# comcon_version_av_reducido.net
KiCad netlist of a schematic drawn in EAGLE
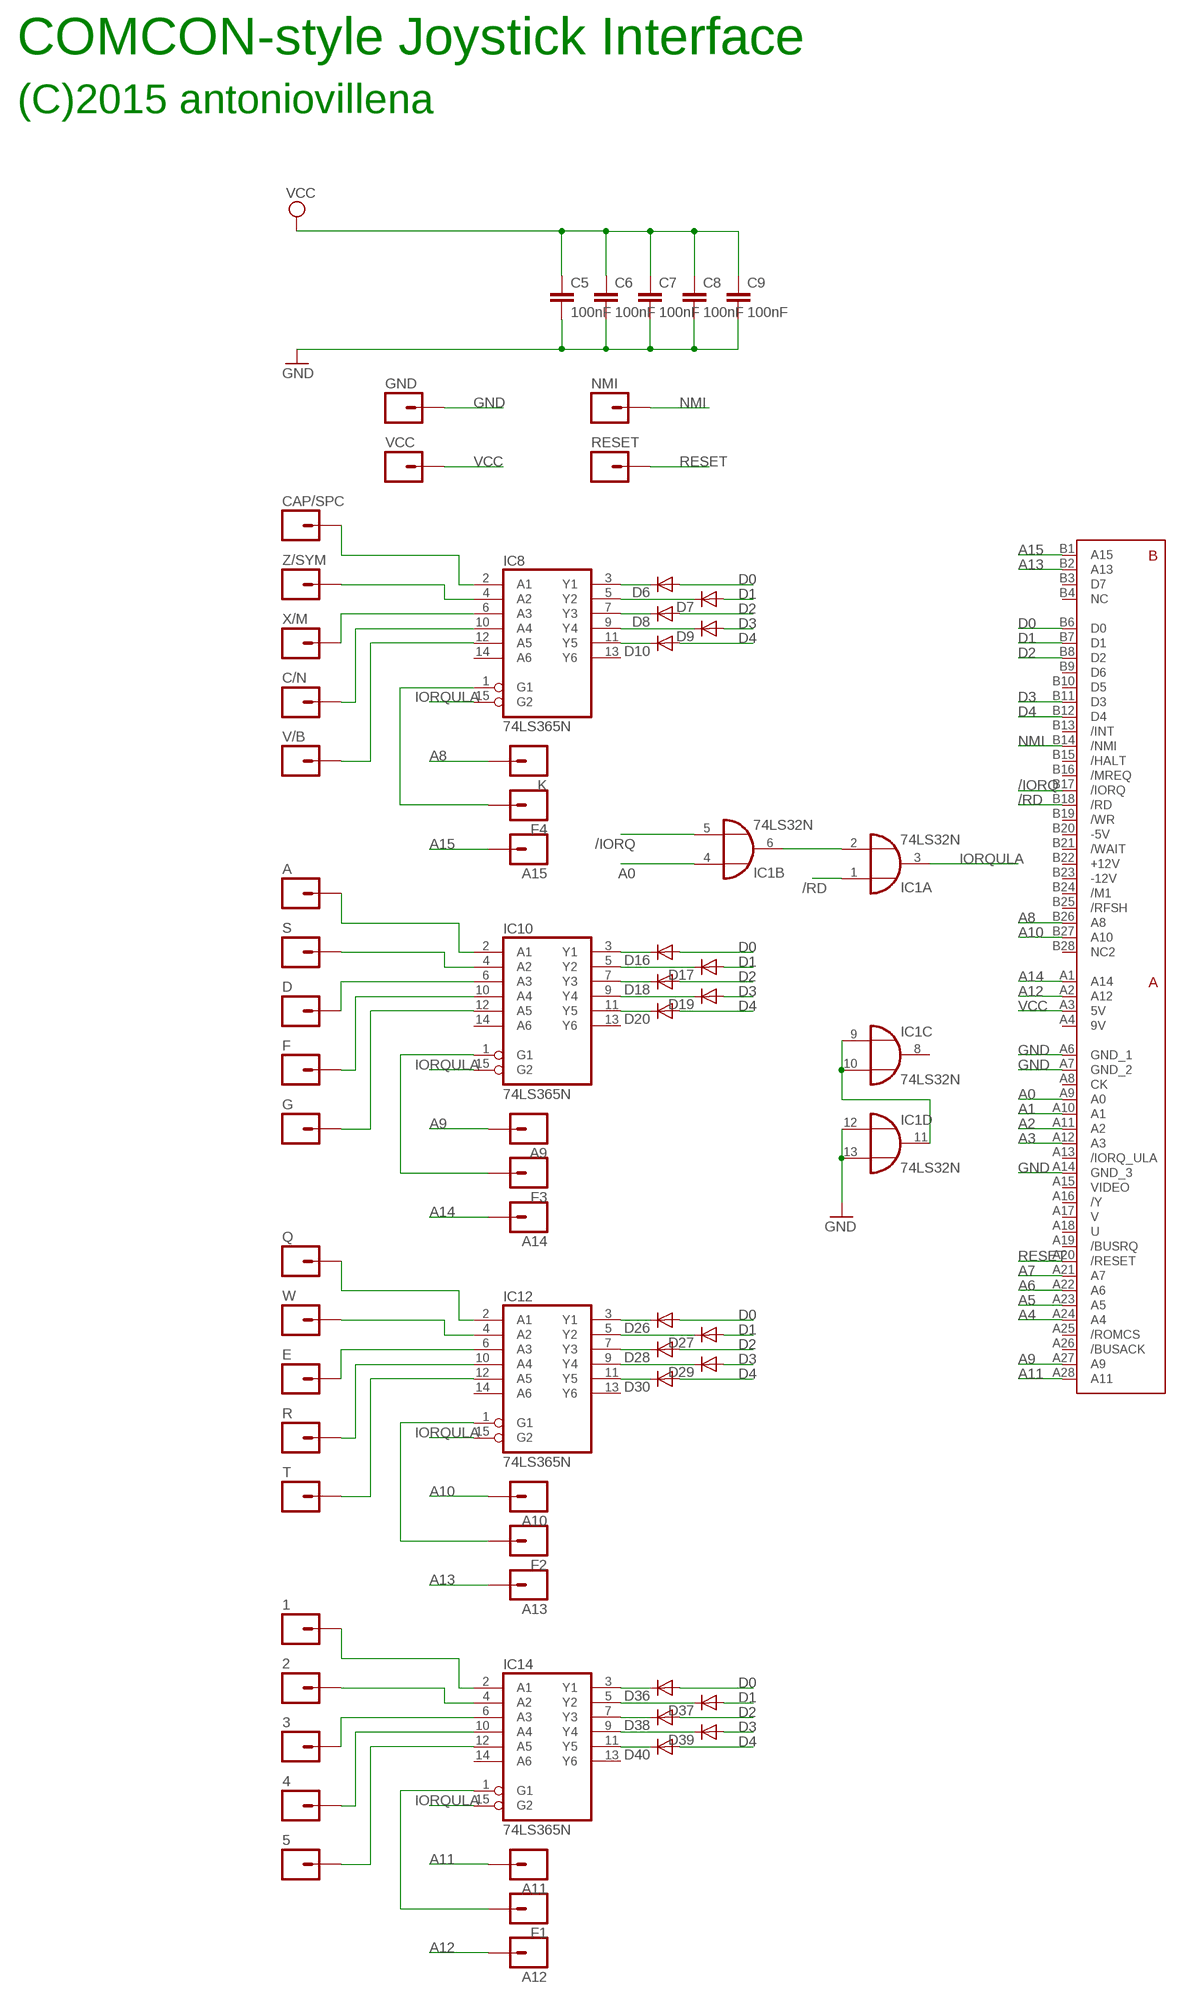
[diagram p0: schematic, sheet 1]

(export (version "E")
  (design (tool "Eeschema 10.0.6"))
  (components
    (comp (ref "1")
      (value "M01PTH")
      (footprint "eagle-import:1X01")
      (libsource (lib "eagle-import") (part "M01PTH"))
    )
    (comp (ref "2")
      (value "M01PTH")
      (footprint "eagle-import:1X01")
      (libsource (lib "eagle-import") (part "M01PTH"))
    )
    (comp (ref "3")
      (value "M01PTH")
      (footprint "eagle-import:1X01")
      (libsource (lib "eagle-import") (part "M01PTH"))
    )
    (comp (ref "4")
      (value "M01PTH")
      (footprint "eagle-import:1X01")
      (libsource (lib "eagle-import") (part "M01PTH"))
    )
    (comp (ref "5")
      (value "M01PTH")
      (footprint "eagle-import:1X01")
      (libsource (lib "eagle-import") (part "M01PTH"))
    )
    (comp (ref "A")
      (value "M01PTH")
      (footprint "eagle-import:1X01")
      (libsource (lib "eagle-import") (part "M01PTH"))
    )
    (comp (ref "A9")
      (value "M01PTH")
      (footprint "eagle-import:1X01")
      (libsource (lib "eagle-import") (part "M01PTH"))
    )
    (comp (ref "A10")
      (value "M01PTH")
      (footprint "eagle-import:1X01")
      (libsource (lib "eagle-import") (part "M01PTH"))
    )
    (comp (ref "A11")
      (value "M01PTH")
      (footprint "eagle-import:1X01")
      (libsource (lib "eagle-import") (part "M01PTH"))
    )
    (comp (ref "A12")
      (value "M01PTH")
      (footprint "eagle-import:1X01")
      (libsource (lib "eagle-import") (part "M01PTH"))
    )
    (comp (ref "A13")
      (value "M01PTH")
      (footprint "eagle-import:1X01")
      (libsource (lib "eagle-import") (part "M01PTH"))
    )
    (comp (ref "A14")
      (value "M01PTH")
      (footprint "eagle-import:1X01")
      (libsource (lib "eagle-import") (part "M01PTH"))
    )
    (comp (ref "A15")
      (value "M01PTH")
      (footprint "eagle-import:1X01")
      (libsource (lib "eagle-import") (part "M01PTH"))
    )
    (comp (ref "C/N")
      (value "M01PTH")
      (footprint "eagle-import:1X01")
      (libsource (lib "eagle-import") (part "M01PTH"))
    )
    (comp (ref "C5")
      (value "100nF")
      (footprint "eagle-import:C050-025X075")
      (libsource (lib "eagle-import") (part "C-EU050-025X075"))
    )
    (comp (ref "C6")
      (value "100nF")
      (footprint "eagle-import:C050-025X075")
      (libsource (lib "eagle-import") (part "C-EU050-025X075"))
    )
    (comp (ref "C7")
      (value "100nF")
      (footprint "eagle-import:C050-025X075")
      (libsource (lib "eagle-import") (part "C-EU050-025X075"))
    )
    (comp (ref "C8")
      (value "100nF")
      (footprint "eagle-import:C050-025X075")
      (libsource (lib "eagle-import") (part "C-EU050-025X075"))
    )
    (comp (ref "C9")
      (value "100nF")
      (footprint "eagle-import:C050-025X075")
      (libsource (lib "eagle-import") (part "C-EU050-025X075"))
    )
    (comp (ref "CAP/SPC")
      (value "M01PTH")
      (footprint "eagle-import:1X01")
      (libsource (lib "eagle-import") (part "M01PTH"))
    )
    (comp (ref "D")
      (value "M01PTH")
      (footprint "eagle-import:1X01")
      (libsource (lib "eagle-import") (part "M01PTH"))
    )
    (comp (ref "D6")
      (value "1N4148DO35-7")
      (footprint "eagle-import:DO35-7")
      (libsource (lib "eagle-import") (part "1N4148DO35-7"))
    )
    (comp (ref "D7")
      (value "1N4148DO35-7")
      (footprint "eagle-import:DO35-7")
      (libsource (lib "eagle-import") (part "1N4148DO35-7"))
    )
    (comp (ref "D8")
      (value "1N4148DO35-7")
      (footprint "eagle-import:DO35-7")
      (libsource (lib "eagle-import") (part "1N4148DO35-7"))
    )
    (comp (ref "D9")
      (value "1N4148DO35-7")
      (footprint "eagle-import:DO35-7")
      (libsource (lib "eagle-import") (part "1N4148DO35-7"))
    )
    (comp (ref "D10")
      (value "1N4148DO35-7")
      (footprint "eagle-import:DO35-7")
      (libsource (lib "eagle-import") (part "1N4148DO35-7"))
    )
    (comp (ref "D16")
      (value "1N4148DO35-7")
      (footprint "eagle-import:DO35-7")
      (libsource (lib "eagle-import") (part "1N4148DO35-7"))
    )
    (comp (ref "D17")
      (value "1N4148DO35-7")
      (footprint "eagle-import:DO35-7")
      (libsource (lib "eagle-import") (part "1N4148DO35-7"))
    )
    (comp (ref "D18")
      (value "1N4148DO35-7")
      (footprint "eagle-import:DO35-7")
      (libsource (lib "eagle-import") (part "1N4148DO35-7"))
    )
    (comp (ref "D19")
      (value "1N4148DO35-7")
      (footprint "eagle-import:DO35-7")
      (libsource (lib "eagle-import") (part "1N4148DO35-7"))
    )
    (comp (ref "D20")
      (value "1N4148DO35-7")
      (footprint "eagle-import:DO35-7")
      (libsource (lib "eagle-import") (part "1N4148DO35-7"))
    )
    (comp (ref "D26")
      (value "1N4148DO35-7")
      (footprint "eagle-import:DO35-7")
      (libsource (lib "eagle-import") (part "1N4148DO35-7"))
    )
    (comp (ref "D27")
      (value "1N4148DO35-7")
      (footprint "eagle-import:DO35-7")
      (libsource (lib "eagle-import") (part "1N4148DO35-7"))
    )
    (comp (ref "D28")
      (value "1N4148DO35-7")
      (footprint "eagle-import:DO35-7")
      (libsource (lib "eagle-import") (part "1N4148DO35-7"))
    )
    (comp (ref "D29")
      (value "1N4148DO35-7")
      (footprint "eagle-import:DO35-7")
      (libsource (lib "eagle-import") (part "1N4148DO35-7"))
    )
    (comp (ref "D30")
      (value "1N4148DO35-7")
      (footprint "eagle-import:DO35-7")
      (libsource (lib "eagle-import") (part "1N4148DO35-7"))
    )
    (comp (ref "D36")
      (value "1N4148DO35-7")
      (footprint "eagle-import:DO35-7")
      (libsource (lib "eagle-import") (part "1N4148DO35-7"))
    )
    (comp (ref "D37")
      (value "1N4148DO35-7")
      (footprint "eagle-import:DO35-7")
      (libsource (lib "eagle-import") (part "1N4148DO35-7"))
    )
    (comp (ref "D38")
      (value "1N4148DO35-7")
      (footprint "eagle-import:DO35-7")
      (libsource (lib "eagle-import") (part "1N4148DO35-7"))
    )
    (comp (ref "D39")
      (value "1N4148DO35-7")
      (footprint "eagle-import:DO35-7")
      (libsource (lib "eagle-import") (part "1N4148DO35-7"))
    )
    (comp (ref "D40")
      (value "1N4148DO35-7")
      (footprint "eagle-import:DO35-7")
      (libsource (lib "eagle-import") (part "1N4148DO35-7"))
    )
    (comp (ref "E")
      (value "M01PTH")
      (footprint "eagle-import:1X01")
      (libsource (lib "eagle-import") (part "M01PTH"))
    )
    (comp (ref "F")
      (value "M01PTH")
      (footprint "eagle-import:1X01")
      (libsource (lib "eagle-import") (part "M01PTH"))
    )
    (comp (ref "F1")
      (value "M01PTH")
      (footprint "eagle-import:1X01")
      (libsource (lib "eagle-import") (part "M01PTH"))
    )
    (comp (ref "F2")
      (value "M01PTH")
      (footprint "eagle-import:1X01")
      (libsource (lib "eagle-import") (part "M01PTH"))
    )
    (comp (ref "F3")
      (value "M01PTH")
      (footprint "eagle-import:1X01")
      (libsource (lib "eagle-import") (part "M01PTH"))
    )
    (comp (ref "F4")
      (value "M01PTH")
      (footprint "eagle-import:1X01")
      (libsource (lib "eagle-import") (part "M01PTH"))
    )
    (comp (ref "G")
      (value "M01PTH")
      (footprint "eagle-import:1X01")
      (libsource (lib "eagle-import") (part "M01PTH"))
    )
    (comp (ref "GND")
      (value "M01PTH")
      (footprint "eagle-import:1X01")
      (libsource (lib "eagle-import") (part "M01PTH"))
    )
    (comp (ref "IC1")
      (value "74LS32N")
      (footprint "eagle-import:DIL14")
      (libsource (lib "eagle-import") (part "7432NLS"))
    )
    (comp (ref "IC8")
      (value "74LS365N")
      (footprint "eagle-import:DIL16")
      (libsource (lib "eagle-import") (part "74365NHC"))
    )
    (comp (ref "IC10")
      (value "74LS365N")
      (footprint "eagle-import:DIL16")
      (libsource (lib "eagle-import") (part "74365NHC"))
    )
    (comp (ref "IC12")
      (value "74LS365N")
      (footprint "eagle-import:DIL16")
      (libsource (lib "eagle-import") (part "74365NHC"))
    )
    (comp (ref "IC14")
      (value "74LS365N")
      (footprint "eagle-import:DIL16")
      (libsource (lib "eagle-import") (part "74365NHC"))
    )
    (comp (ref "K")
      (value "M01PTH")
      (footprint "eagle-import:1X01")
      (libsource (lib "eagle-import") (part "M01PTH"))
    )
    (comp (ref "NMI")
      (value "M01PTH")
      (footprint "eagle-import:1X01")
      (libsource (lib "eagle-import") (part "M01PTH"))
    )
    (comp (ref "Q")
      (value "M01PTH")
      (footprint "eagle-import:1X01")
      (libsource (lib "eagle-import") (part "M01PTH"))
    )
    (comp (ref "R")
      (value "M01PTH")
      (footprint "eagle-import:1X01")
      (libsource (lib "eagle-import") (part "M01PTH"))
    )
    (comp (ref "RESET")
      (value "M01PTH")
      (footprint "eagle-import:1X01")
      (libsource (lib "eagle-import") (part "M01PTH"))
    )
    (comp (ref "S")
      (value "M01PTH")
      (footprint "eagle-import:1X01")
      (libsource (lib "eagle-import") (part "M01PTH"))
    )
    (comp (ref "T")
      (value "M01PTH")
      (footprint "eagle-import:1X01")
      (libsource (lib "eagle-import") (part "M01PTH"))
    )
    (comp (ref "U$3")
      (value "ZXSP_ED2X28_SPE")
      (footprint "eagle-import:2X28_SPE")
      (libsource (lib "eagle-import") (part "ZXSP_ED2X28_SPE"))
    )
    (comp (ref "V/B")
      (value "M01PTH")
      (footprint "eagle-import:1X01")
      (libsource (lib "eagle-import") (part "M01PTH"))
    )
    (comp (ref "VCC")
      (value "M01PTH")
      (footprint "eagle-import:1X01")
      (libsource (lib "eagle-import") (part "M01PTH"))
    )
    (comp (ref "W")
      (value "M01PTH")
      (footprint "eagle-import:1X01")
      (libsource (lib "eagle-import") (part "M01PTH"))
    )
    (comp (ref "X/M")
      (value "M01PTH")
      (footprint "eagle-import:1X01")
      (libsource (lib "eagle-import") (part "M01PTH"))
    )
    (comp (ref "Z/SYM")
      (value "M01PTH")
      (footprint "eagle-import:1X01")
      (libsource (lib "eagle-import") (part "M01PTH"))
    )
  )
  (nets
    (net (code "1") (name "/+12V") (class "Default")
      (node (ref "U$3") (pin "B22") (pinfunction "+12V_B22") (pintype "power_in"))
    )
    (net (code "2") (name "/-5V") (class "Default")
      (node (ref "U$3") (pin "B20") (pinfunction "-5V_B20") (pintype "power_in"))
    )
    (net (code "3") (name "/-12V") (class "Default")
      (node (ref "U$3") (pin "B23") (pinfunction "-12V_B23") (pintype "power_in"))
    )
    (net (code "4") (name "/9V") (class "Default")
      (node (ref "U$3") (pin "A4") (pinfunction "9V_A4") (pintype "power_in"))
    )
    (net (code "5") (name "/A0") (class "Default")
      (node (ref "IC1") (pin "4") (pinfunction "I0_4") (pintype "input"))
      (node (ref "U$3") (pin "A9") (pinfunction "A0_A9") (pintype "bidirectional"))
    )
    (net (code "6") (name "/A1") (class "Default")
      (node (ref "U$3") (pin "A10") (pinfunction "A1_A10") (pintype "bidirectional"))
    )
    (net (code "7") (name "/A2") (class "Default")
      (node (ref "U$3") (pin "A11") (pinfunction "A2_A11") (pintype "bidirectional"))
    )
    (net (code "8") (name "/A3") (class "Default")
      (node (ref "U$3") (pin "A12") (pinfunction "A3_A12") (pintype "bidirectional"))
    )
    (net (code "9") (name "/A4") (class "Default")
      (node (ref "U$3") (pin "A24") (pinfunction "A4_A24") (pintype "bidirectional"))
    )
    (net (code "10") (name "/A5") (class "Default")
      (node (ref "U$3") (pin "A23") (pinfunction "A5_A23") (pintype "bidirectional"))
    )
    (net (code "11") (name "/A6") (class "Default")
      (node (ref "U$3") (pin "A22") (pinfunction "A6_A22") (pintype "bidirectional"))
    )
    (net (code "12") (name "/A7") (class "Default")
      (node (ref "U$3") (pin "A21") (pinfunction "A7_A21") (pintype "bidirectional"))
    )
    (net (code "13") (name "/A8") (class "Default")
      (node (ref "K") (pin "1") (pinfunction "1_1") (pintype "passive"))
      (node (ref "U$3") (pin "B26") (pinfunction "A8_B26") (pintype "bidirectional"))
    )
    (net (code "14") (name "/A9") (class "Default")
      (node (ref "A9") (pin "1") (pinfunction "1_1") (pintype "passive"))
      (node (ref "U$3") (pin "A27") (pinfunction "A9_A27") (pintype "bidirectional"))
    )
    (net (code "15") (name "/A10") (class "Default")
      (node (ref "A10") (pin "1") (pinfunction "1_1") (pintype "passive"))
      (node (ref "U$3") (pin "B27") (pinfunction "A10_B27") (pintype "bidirectional"))
    )
    (net (code "16") (name "/A11") (class "Default")
      (node (ref "A11") (pin "1") (pinfunction "1_1") (pintype "passive"))
      (node (ref "U$3") (pin "A28") (pinfunction "A11_A28") (pintype "bidirectional"))
    )
    (net (code "17") (name "/A12") (class "Default")
      (node (ref "A12") (pin "1") (pinfunction "1_1") (pintype "passive"))
      (node (ref "U$3") (pin "A2") (pinfunction "A12_A2") (pintype "bidirectional"))
    )
    (net (code "18") (name "/A13") (class "Default")
      (node (ref "A13") (pin "1") (pinfunction "1_1") (pintype "passive"))
      (node (ref "U$3") (pin "B2") (pinfunction "A13_B2") (pintype "bidirectional"))
    )
    (net (code "19") (name "/A14") (class "Default")
      (node (ref "A14") (pin "1") (pinfunction "1_1") (pintype "passive"))
      (node (ref "U$3") (pin "A1") (pinfunction "A14_A1") (pintype "bidirectional"))
    )
    (net (code "20") (name "/A15") (class "Default")
      (node (ref "A15") (pin "1") (pinfunction "1_1") (pintype "passive"))
      (node (ref "U$3") (pin "B1") (pinfunction "A15_B1") (pintype "bidirectional"))
    )
    (net (code "21") (name "/D0") (class "Default")
      (node (ref "D16") (pin "A") (pinfunction "A_A") (pintype "passive"))
      (node (ref "D26") (pin "A") (pinfunction "A_A") (pintype "passive"))
      (node (ref "D36") (pin "A") (pinfunction "A_A") (pintype "passive"))
      (node (ref "D6") (pin "A") (pinfunction "A_A") (pintype "passive"))
      (node (ref "U$3") (pin "B6") (pinfunction "D0_B6") (pintype "bidirectional"))
    )
    (net (code "22") (name "/D1") (class "Default")
      (node (ref "D17") (pin "A") (pinfunction "A_A") (pintype "passive"))
      (node (ref "D27") (pin "A") (pinfunction "A_A") (pintype "passive"))
      (node (ref "D37") (pin "A") (pinfunction "A_A") (pintype "passive"))
      (node (ref "D7") (pin "A") (pinfunction "A_A") (pintype "passive"))
      (node (ref "U$3") (pin "B7") (pinfunction "D1_B7") (pintype "bidirectional"))
    )
    (net (code "23") (name "/D2") (class "Default")
      (node (ref "D18") (pin "A") (pinfunction "A_A") (pintype "passive"))
      (node (ref "D28") (pin "A") (pinfunction "A_A") (pintype "passive"))
      (node (ref "D38") (pin "A") (pinfunction "A_A") (pintype "passive"))
      (node (ref "D8") (pin "A") (pinfunction "A_A") (pintype "passive"))
      (node (ref "U$3") (pin "B8") (pinfunction "D2_B8") (pintype "bidirectional"))
    )
    (net (code "24") (name "/D3") (class "Default")
      (node (ref "D19") (pin "A") (pinfunction "A_A") (pintype "passive"))
      (node (ref "D29") (pin "A") (pinfunction "A_A") (pintype "passive"))
      (node (ref "D39") (pin "A") (pinfunction "A_A") (pintype "passive"))
      (node (ref "D9") (pin "A") (pinfunction "A_A") (pintype "passive"))
      (node (ref "U$3") (pin "B11") (pinfunction "D3_B11") (pintype "bidirectional"))
    )
    (net (code "25") (name "/D4") (class "Default")
      (node (ref "D10") (pin "A") (pinfunction "A_A") (pintype "passive"))
      (node (ref "D20") (pin "A") (pinfunction "A_A") (pintype "passive"))
      (node (ref "D30") (pin "A") (pinfunction "A_A") (pintype "passive"))
      (node (ref "D40") (pin "A") (pinfunction "A_A") (pintype "passive"))
      (node (ref "U$3") (pin "B12") (pinfunction "D4_B12") (pintype "bidirectional"))
    )
    (net (code "26") (name "/IORQULA") (class "Default")
      (node (ref "IC1") (pin "3") (pinfunction "O_3") (pintype "output"))
      (node (ref "IC10") (pin "15") (pinfunction "G2_15") (pintype "input"))
      (node (ref "IC12") (pin "15") (pinfunction "G2_15") (pintype "input"))
      (node (ref "IC14") (pin "15") (pinfunction "G2_15") (pintype "input"))
      (node (ref "IC8") (pin "15") (pinfunction "G2_15") (pintype "input"))
    )
    (net (code "27") (name "/NMI") (class "Default")
      (node (ref "NMI") (pin "1") (pinfunction "1_1") (pintype "passive"))
      (node (ref "U$3") (pin "B14") (pinfunction "/NMI_B14") (pintype "bidirectional"))
    )
    (net (code "28") (name "/RESET") (class "Default")
      (node (ref "RESET") (pin "1") (pinfunction "1_1") (pintype "passive"))
      (node (ref "U$3") (pin "A20") (pinfunction "/RESET_A20") (pintype "bidirectional"))
    )
    (net (code "29") (name "/{slash}IORQ") (class "Default")
      (node (ref "IC1") (pin "5") (pinfunction "I1_5") (pintype "input"))
      (node (ref "U$3") (pin "B17") (pinfunction "/IORQ_B17") (pintype "bidirectional"))
    )
    (net (code "30") (name "/{slash}RD") (class "Default")
      (node (ref "IC1") (pin "1") (pinfunction "I0_1") (pintype "input"))
      (node (ref "U$3") (pin "B18") (pinfunction "/RD_B18") (pintype "bidirectional"))
    )
    (net (code "31") (name "GND") (class "Default")
      (node (ref "C5") (pin "2") (pinfunction "2_2") (pintype "passive"))
      (node (ref "C6") (pin "2") (pinfunction "2_2") (pintype "passive"))
      (node (ref "C7") (pin "2") (pinfunction "2_2") (pintype "passive"))
      (node (ref "C8") (pin "2") (pinfunction "2_2") (pintype "passive"))
      (node (ref "C9") (pin "2") (pinfunction "2_2") (pintype "passive"))
      (node (ref "GND") (pin "1") (pinfunction "1_1") (pintype "passive"))
      (node (ref "IC1") (pin "12") (pinfunction "I0_12") (pintype "input"))
      (node (ref "IC1") (pin "13") (pinfunction "I1_13") (pintype "input"))
      (node (ref "U$3") (pin "A14") (pinfunction "GND_3_A14") (pintype "power_in"))
      (node (ref "U$3") (pin "A6") (pinfunction "GND_1_A6") (pintype "power_in"))
      (node (ref "U$3") (pin "A7") (pinfunction "GND_2_A7") (pintype "power_in"))
    )
    (net (code "32") (name "Net-(IC1A-I1)") (class "Default")
      (node (ref "IC1") (pin "2") (pinfunction "I1_2") (pintype "input"))
      (node (ref "IC1") (pin "6") (pinfunction "O_6") (pintype "output"))
    )
    (net (code "33") (name "Net-(IC1C-I0)") (class "Default")
      (node (ref "IC1") (pin "10") (pinfunction "I1_10") (pintype "input"))
      (node (ref "IC1") (pin "11") (pinfunction "O_11") (pintype "output"))
      (node (ref "IC1") (pin "9") (pinfunction "I0_9") (pintype "input"))
    )
    (net (code "34") (name "Net-(IC8A-A1)") (class "Default")
      (node (ref "CAP/SPC") (pin "1") (pinfunction "1_1") (pintype "passive"))
      (node (ref "IC8") (pin "2") (pinfunction "A1_2") (pintype "input"))
    )
    (net (code "35") (name "Net-(IC8A-A2)") (class "Default")
      (node (ref "IC8") (pin "4") (pinfunction "A2_4") (pintype "input"))
      (node (ref "Z/SYM") (pin "1") (pinfunction "1_1") (pintype "passive"))
    )
    (net (code "36") (name "Net-(IC8A-A3)") (class "Default")
      (node (ref "IC8") (pin "6") (pinfunction "A3_6") (pintype "input"))
      (node (ref "X/M") (pin "1") (pinfunction "1_1") (pintype "passive"))
    )
    (net (code "37") (name "Net-(IC8A-A4)") (class "Default")
      (node (ref "C/N") (pin "1") (pinfunction "1_1") (pintype "passive"))
      (node (ref "IC8") (pin "10") (pinfunction "A4_10") (pintype "input"))
    )
    (net (code "38") (name "Net-(IC8A-A5)") (class "Default")
      (node (ref "IC8") (pin "12") (pinfunction "A5_12") (pintype "input"))
      (node (ref "V/B") (pin "1") (pinfunction "1_1") (pintype "passive"))
    )
    (net (code "39") (name "Net-(IC8A-G1)") (class "Default")
      (node (ref "F4") (pin "1") (pinfunction "1_1") (pintype "passive"))
      (node (ref "IC8") (pin "1") (pinfunction "G1_1") (pintype "input"))
    )
    (net (code "40") (name "Net-(IC8A-Y1)") (class "Default")
      (node (ref "D6") (pin "C") (pinfunction "C_C") (pintype "passive"))
      (node (ref "IC8") (pin "3") (pinfunction "Y1_3") (pintype "tri_state"))
    )
    (net (code "41") (name "Net-(IC8A-Y2)") (class "Default")
      (node (ref "D7") (pin "C") (pinfunction "C_C") (pintype "passive"))
      (node (ref "IC8") (pin "5") (pinfunction "Y2_5") (pintype "tri_state"))
    )
    (net (code "42") (name "Net-(IC8A-Y3)") (class "Default")
      (node (ref "D8") (pin "C") (pinfunction "C_C") (pintype "passive"))
      (node (ref "IC8") (pin "7") (pinfunction "Y3_7") (pintype "tri_state"))
    )
    (net (code "43") (name "Net-(IC8A-Y4)") (class "Default")
      (node (ref "D9") (pin "C") (pinfunction "C_C") (pintype "passive"))
      (node (ref "IC8") (pin "9") (pinfunction "Y4_9") (pintype "tri_state"))
    )
    (net (code "44") (name "Net-(IC8A-Y5)") (class "Default")
      (node (ref "D10") (pin "C") (pinfunction "C_C") (pintype "passive"))
      (node (ref "IC8") (pin "11") (pinfunction "Y5_11") (pintype "tri_state"))
    )
    (net (code "45") (name "Net-(IC10A-A1)") (class "Default")
      (node (ref "A") (pin "1") (pinfunction "1_1") (pintype "passive"))
      (node (ref "IC10") (pin "2") (pinfunction "A1_2") (pintype "input"))
    )
    (net (code "46") (name "Net-(IC10A-A2)") (class "Default")
      (node (ref "IC10") (pin "4") (pinfunction "A2_4") (pintype "input"))
      (node (ref "S") (pin "1") (pinfunction "1_1") (pintype "passive"))
    )
    (net (code "47") (name "Net-(IC10A-A3)") (class "Default")
      (node (ref "D") (pin "1") (pinfunction "1_1") (pintype "passive"))
      (node (ref "IC10") (pin "6") (pinfunction "A3_6") (pintype "input"))
    )
    (net (code "48") (name "Net-(IC10A-A4)") (class "Default")
      (node (ref "F") (pin "1") (pinfunction "1_1") (pintype "passive"))
      (node (ref "IC10") (pin "10") (pinfunction "A4_10") (pintype "input"))
    )
    (net (code "49") (name "Net-(IC10A-A5)") (class "Default")
      (node (ref "G") (pin "1") (pinfunction "1_1") (pintype "passive"))
      (node (ref "IC10") (pin "12") (pinfunction "A5_12") (pintype "input"))
    )
    (net (code "50") (name "Net-(IC10A-G1)") (class "Default")
      (node (ref "F3") (pin "1") (pinfunction "1_1") (pintype "passive"))
      (node (ref "IC10") (pin "1") (pinfunction "G1_1") (pintype "input"))
    )
    (net (code "51") (name "Net-(IC10A-Y1)") (class "Default")
      (node (ref "D16") (pin "C") (pinfunction "C_C") (pintype "passive"))
      (node (ref "IC10") (pin "3") (pinfunction "Y1_3") (pintype "tri_state"))
    )
    (net (code "52") (name "Net-(IC10A-Y2)") (class "Default")
      (node (ref "D17") (pin "C") (pinfunction "C_C") (pintype "passive"))
      (node (ref "IC10") (pin "5") (pinfunction "Y2_5") (pintype "tri_state"))
    )
    (net (code "53") (name "Net-(IC10A-Y3)") (class "Default")
      (node (ref "D18") (pin "C") (pinfunction "C_C") (pintype "passive"))
      (node (ref "IC10") (pin "7") (pinfunction "Y3_7") (pintype "tri_state"))
    )
    (net (code "54") (name "Net-(IC10A-Y4)") (class "Default")
      (node (ref "D19") (pin "C") (pinfunction "C_C") (pintype "passive"))
      (node (ref "IC10") (pin "9") (pinfunction "Y4_9") (pintype "tri_state"))
    )
    (net (code "55") (name "Net-(IC10A-Y5)") (class "Default")
      (node (ref "D20") (pin "C") (pinfunction "C_C") (pintype "passive"))
      (node (ref "IC10") (pin "11") (pinfunction "Y5_11") (pintype "tri_state"))
    )
    (net (code "56") (name "Net-(IC12A-A1)") (class "Default")
      (node (ref "IC12") (pin "2") (pinfunction "A1_2") (pintype "input"))
      (node (ref "Q") (pin "1") (pinfunction "1_1") (pintype "passive"))
    )
    (net (code "57") (name "Net-(IC12A-A2)") (class "Default")
      (node (ref "IC12") (pin "4") (pinfunction "A2_4") (pintype "input"))
      (node (ref "W") (pin "1") (pinfunction "1_1") (pintype "passive"))
    )
    (net (code "58") (name "Net-(IC12A-A3)") (class "Default")
      (node (ref "E") (pin "1") (pinfunction "1_1") (pintype "passive"))
      (node (ref "IC12") (pin "6") (pinfunction "A3_6") (pintype "input"))
    )
    (net (code "59") (name "Net-(IC12A-A4)") (class "Default")
      (node (ref "IC12") (pin "10") (pinfunction "A4_10") (pintype "input"))
      (node (ref "R") (pin "1") (pinfunction "1_1") (pintype "passive"))
    )
    (net (code "60") (name "Net-(IC12A-A5)") (class "Default")
      (node (ref "IC12") (pin "12") (pinfunction "A5_12") (pintype "input"))
      (node (ref "T") (pin "1") (pinfunction "1_1") (pintype "passive"))
    )
    (net (code "61") (name "Net-(IC12A-G1)") (class "Default")
      (node (ref "F2") (pin "1") (pinfunction "1_1") (pintype "passive"))
      (node (ref "IC12") (pin "1") (pinfunction "G1_1") (pintype "input"))
    )
    (net (code "62") (name "Net-(IC12A-Y1)") (class "Default")
      (node (ref "D26") (pin "C") (pinfunction "C_C") (pintype "passive"))
      (node (ref "IC12") (pin "3") (pinfunction "Y1_3") (pintype "tri_state"))
    )
    (net (code "63") (name "Net-(IC12A-Y2)") (class "Default")
      (node (ref "D27") (pin "C") (pinfunction "C_C") (pintype "passive"))
      (node (ref "IC12") (pin "5") (pinfunction "Y2_5") (pintype "tri_state"))
    )
    (net (code "64") (name "Net-(IC12A-Y3)") (class "Default")
      (node (ref "D28") (pin "C") (pinfunction "C_C") (pintype "passive"))
      (node (ref "IC12") (pin "7") (pinfunction "Y3_7") (pintype "tri_state"))
    )
    (net (code "65") (name "Net-(IC12A-Y4)") (class "Default")
      (node (ref "D29") (pin "C") (pinfunction "C_C") (pintype "passive"))
      (node (ref "IC12") (pin "9") (pinfunction "Y4_9") (pintype "tri_state"))
    )
    (net (code "66") (name "Net-(IC12A-Y5)") (class "Default")
      (node (ref "D30") (pin "C") (pinfunction "C_C") (pintype "passive"))
      (node (ref "IC12") (pin "11") (pinfunction "Y5_11") (pintype "tri_state"))
    )
    (net (code "67") (name "Net-(IC14A-A1)") (class "Default")
      (node (ref "1") (pin "1") (pinfunction "1_1") (pintype "passive"))
      (node (ref "IC14") (pin "2") (pinfunction "A1_2") (pintype "input"))
    )
    (net (code "68") (name "Net-(IC14A-A2)") (class "Default")
      (node (ref "2") (pin "1") (pinfunction "1_1") (pintype "passive"))
      (node (ref "IC14") (pin "4") (pinfunction "A2_4") (pintype "input"))
    )
    (net (code "69") (name "Net-(IC14A-A3)") (class "Default")
      (node (ref "3") (pin "1") (pinfunction "1_1") (pintype "passive"))
      (node (ref "IC14") (pin "6") (pinfunction "A3_6") (pintype "input"))
    )
    (net (code "70") (name "Net-(IC14A-A4)") (class "Default")
      (node (ref "4") (pin "1") (pinfunction "1_1") (pintype "passive"))
      (node (ref "IC14") (pin "10") (pinfunction "A4_10") (pintype "input"))
    )
    (net (code "71") (name "Net-(IC14A-A5)") (class "Default")
      (node (ref "5") (pin "1") (pinfunction "1_1") (pintype "passive"))
      (node (ref "IC14") (pin "12") (pinfunction "A5_12") (pintype "input"))
    )
    (net (code "72") (name "Net-(IC14A-G1)") (class "Default")
      (node (ref "F1") (pin "1") (pinfunction "1_1") (pintype "passive"))
      (node (ref "IC14") (pin "1") (pinfunction "G1_1") (pintype "input"))
    )
    (net (code "73") (name "Net-(IC14A-Y1)") (class "Default")
      (node (ref "D36") (pin "C") (pinfunction "C_C") (pintype "passive"))
      (node (ref "IC14") (pin "3") (pinfunction "Y1_3") (pintype "tri_state"))
    )
    (net (code "74") (name "Net-(IC14A-Y2)") (class "Default")
      (node (ref "D37") (pin "C") (pinfunction "C_C") (pintype "passive"))
      (node (ref "IC14") (pin "5") (pinfunction "Y2_5") (pintype "tri_state"))
    )
    (net (code "75") (name "Net-(IC14A-Y3)") (class "Default")
      (node (ref "D38") (pin "C") (pinfunction "C_C") (pintype "passive"))
      (node (ref "IC14") (pin "7") (pinfunction "Y3_7") (pintype "tri_state"))
    )
    (net (code "76") (name "Net-(IC14A-Y4)") (class "Default")
      (node (ref "D39") (pin "C") (pinfunction "C_C") (pintype "passive"))
      (node (ref "IC14") (pin "9") (pinfunction "Y4_9") (pintype "tri_state"))
    )
    (net (code "77") (name "Net-(IC14A-Y5)") (class "Default")
      (node (ref "D40") (pin "C") (pinfunction "C_C") (pintype "passive"))
      (node (ref "IC14") (pin "11") (pinfunction "Y5_11") (pintype "tri_state"))
    )
    (net (code "78") (name "VCC") (class "Default")
      (node (ref "C5") (pin "1") (pinfunction "1_1") (pintype "passive"))
      (node (ref "C6") (pin "1") (pinfunction "1_1") (pintype "passive"))
      (node (ref "C7") (pin "1") (pinfunction "1_1") (pintype "passive"))
      (node (ref "C8") (pin "1") (pinfunction "1_1") (pintype "passive"))
      (node (ref "C9") (pin "1") (pinfunction "1_1") (pintype "passive"))
      (node (ref "U$3") (pin "A3") (pinfunction "5V_A3") (pintype "power_in"))
      (node (ref "VCC") (pin "1") (pinfunction "1_1") (pintype "passive"))
    )
    (net (code "79") (name "unconnected-(IC1C-O-Pad8)") (class "Default")
      (node (ref "IC1") (pin "8") (pinfunction "O_8") (pintype "output"))
    )
    (net (code "80") (name "unconnected-(IC8A-A6-Pad14)") (class "Default")
      (node (ref "IC8") (pin "14") (pinfunction "A6_14") (pintype "input"))
    )
    (net (code "81") (name "unconnected-(IC8A-Y6-Pad13)") (class "Default")
      (node (ref "IC8") (pin "13") (pinfunction "Y6_13") (pintype "tri_state"))
    )
    (net (code "82") (name "unconnected-(IC10A-A6-Pad14)") (class "Default")
      (node (ref "IC10") (pin "14") (pinfunction "A6_14") (pintype "input"))
    )
    (net (code "83") (name "unconnected-(IC10A-Y6-Pad13)") (class "Default")
      (node (ref "IC10") (pin "13") (pinfunction "Y6_13") (pintype "tri_state"))
    )
    (net (code "84") (name "unconnected-(IC12A-A6-Pad14)") (class "Default")
      (node (ref "IC12") (pin "14") (pinfunction "A6_14") (pintype "input"))
    )
    (net (code "85") (name "unconnected-(IC12A-Y6-Pad13)") (class "Default")
      (node (ref "IC12") (pin "13") (pinfunction "Y6_13") (pintype "tri_state"))
    )
    (net (code "86") (name "unconnected-(IC14A-A6-Pad14)") (class "Default")
      (node (ref "IC14") (pin "14") (pinfunction "A6_14") (pintype "input"))
    )
    (net (code "87") (name "unconnected-(IC14A-Y6-Pad13)") (class "Default")
      (node (ref "IC14") (pin "13") (pinfunction "Y6_13") (pintype "tri_state"))
    )
    (net (code "88") (name "unconnected-(U$3-CK-PadA8)") (class "Default")
      (node (ref "U$3") (pin "A8") (pinfunction "CK_A8") (pintype "bidirectional"))
    )
    (net (code "89") (name "unconnected-(U$3-D5-PadB10)") (class "Default")
      (node (ref "U$3") (pin "B10") (pinfunction "D5_B10") (pintype "bidirectional"))
    )
    (net (code "90") (name "unconnected-(U$3-D6-PadB9)") (class "Default")
      (node (ref "U$3") (pin "B9") (pinfunction "D6_B9") (pintype "bidirectional"))
    )
    (net (code "91") (name "unconnected-(U$3-D7-PadB3)") (class "Default")
      (node (ref "U$3") (pin "B3") (pinfunction "D7_B3") (pintype "bidirectional"))
    )
    (net (code "92") (name "unconnected-(U$3-NC-PadB4)") (class "Default")
      (node (ref "U$3") (pin "B4") (pinfunction "NC_B4") (pintype "no_connect"))
    )
    (net (code "93") (name "unconnected-(U$3-NC2-PadB28)") (class "Default")
      (node (ref "U$3") (pin "B28") (pinfunction "NC2_B28") (pintype "no_connect"))
    )
    (net (code "94") (name "unconnected-(U$3-U-PadA18)") (class "Default")
      (node (ref "U$3") (pin "A18") (pinfunction "U_A18") (pintype "bidirectional"))
    )
    (net (code "95") (name "unconnected-(U$3-V-PadA17)") (class "Default")
      (node (ref "U$3") (pin "A17") (pinfunction "V_A17") (pintype "bidirectional"))
    )
    (net (code "96") (name "unconnected-(U$3-VIDEO-PadA15)") (class "Default")
      (node (ref "U$3") (pin "A15") (pinfunction "VIDEO_A15") (pintype "bidirectional"))
    )
    (net (code "97") (name "unconnected-(U$3-{slash}BUSACK-PadA26)") (class "Default")
      (node (ref "U$3") (pin "A26") (pinfunction "/BUSACK_A26") (pintype "bidirectional"))
    )
    (net (code "98") (name "unconnected-(U$3-{slash}BUSRQ-PadA19)") (class "Default")
      (node (ref "U$3") (pin "A19") (pinfunction "/BUSRQ_A19") (pintype "bidirectional"))
    )
    (net (code "99") (name "unconnected-(U$3-{slash}HALT-PadB15)") (class "Default")
      (node (ref "U$3") (pin "B15") (pinfunction "/HALT_B15") (pintype "bidirectional"))
    )
    (net (code "100") (name "unconnected-(U$3-{slash}INT-PadB13)") (class "Default")
      (node (ref "U$3") (pin "B13") (pinfunction "/INT_B13") (pintype "bidirectional"))
    )
    (net (code "101") (name "unconnected-(U$3-{slash}IORQ_ULA-PadA13)") (class "Default")
      (node (ref "U$3") (pin "A13") (pinfunction "/IORQ_ULA_A13") (pintype "bidirectional"))
    )
    (net (code "102") (name "unconnected-(U$3-{slash}M1-PadB24)") (class "Default")
      (node (ref "U$3") (pin "B24") (pinfunction "/M1_B24") (pintype "bidirectional"))
    )
    (net (code "103") (name "unconnected-(U$3-{slash}MREQ-PadB16)") (class "Default")
      (node (ref "U$3") (pin "B16") (pinfunction "/MREQ_B16") (pintype "bidirectional"))
    )
    (net (code "104") (name "unconnected-(U$3-{slash}RFSH-PadB25)") (class "Default")
      (node (ref "U$3") (pin "B25") (pinfunction "/RFSH_B25") (pintype "bidirectional"))
    )
    (net (code "105") (name "unconnected-(U$3-{slash}ROMCS-PadA25)") (class "Default")
      (node (ref "U$3") (pin "A25") (pinfunction "/ROMCS_A25") (pintype "bidirectional"))
    )
    (net (code "106") (name "unconnected-(U$3-{slash}WAIT-PadB21)") (class "Default")
      (node (ref "U$3") (pin "B21") (pinfunction "/WAIT_B21") (pintype "bidirectional"))
    )
    (net (code "107") (name "unconnected-(U$3-{slash}WR-PadB19)") (class "Default")
      (node (ref "U$3") (pin "B19") (pinfunction "/WR_B19") (pintype "bidirectional"))
    )
    (net (code "108") (name "unconnected-(U$3-{slash}Y-PadA16)") (class "Default")
      (node (ref "U$3") (pin "A16") (pinfunction "/Y_A16") (pintype "bidirectional"))
    )
  )
)
